# driver_board_one_module_pic_v2.net
KiCad netlist of a schematic drawn in EAGLE
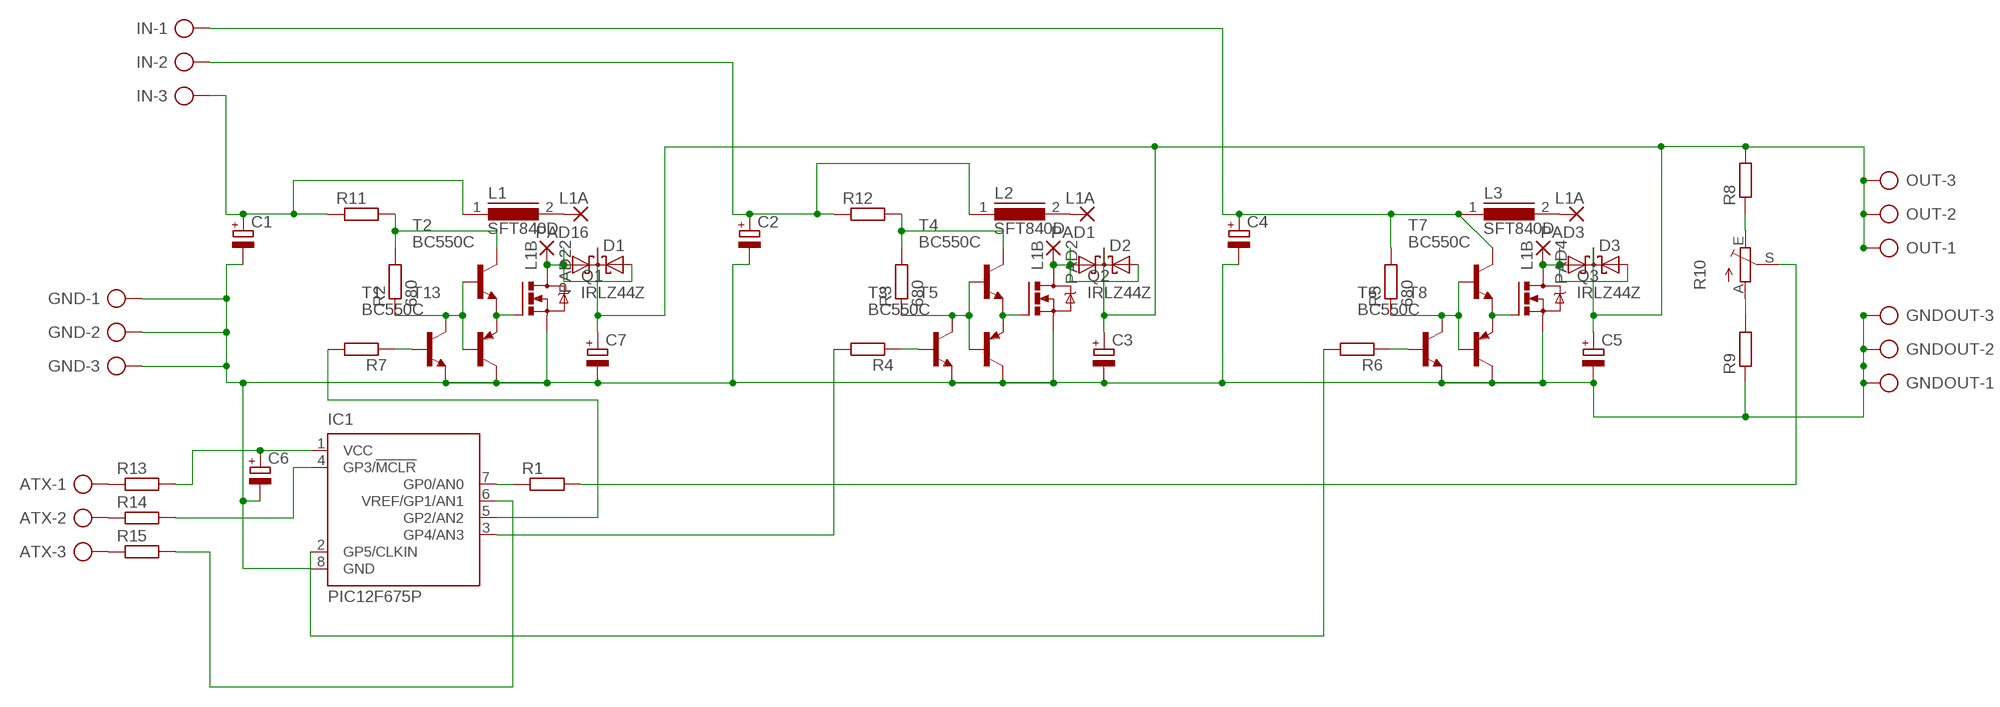
[diagram p0: schematic, sheet 1]

(export (version "E")
  (design (tool "Eeschema 10.0.6"))
  (components
    (comp (ref "ATX")
      (value "AK300/3")
      (footprint "eagle-import:AK300_3")
      (libsource (lib "eagle-import") (part "AK300/3"))
    )
    (comp (ref "C1")
      (value "CPOL-EUE5-8.5")
      (footprint "eagle-import:E5-8,5")
      (libsource (lib "eagle-import") (part "CPOL-EUE5-8.5"))
    )
    (comp (ref "C2")
      (value "CPOL-EUE5-8.5")
      (footprint "eagle-import:E5-8,5")
      (libsource (lib "eagle-import") (part "CPOL-EUE5-8.5"))
    )
    (comp (ref "C3")
      (value "CPOL-EUE5-8.5")
      (footprint "eagle-import:E5-8,5")
      (libsource (lib "eagle-import") (part "CPOL-EUE5-8.5"))
    )
    (comp (ref "C4")
      (value "CPOL-EUE5-8.5")
      (footprint "eagle-import:E5-8,5")
      (libsource (lib "eagle-import") (part "CPOL-EUE5-8.5"))
    )
    (comp (ref "C5")
      (value "CPOL-EUE5-8.5")
      (footprint "eagle-import:E5-8,5")
      (libsource (lib "eagle-import") (part "CPOL-EUE5-8.5"))
    )
    (comp (ref "C6")
      (value "CPOL-EUE5-8.5")
      (footprint "eagle-import:E5-8,5")
      (libsource (lib "eagle-import") (part "CPOL-EUE5-8.5"))
    )
    (comp (ref "C7")
      (value "CPOL-EUE5-8.5")
      (footprint "eagle-import:E5-8,5")
      (libsource (lib "eagle-import") (part "CPOL-EUE5-8.5"))
    )
    (comp (ref "D1")
      (value "DIODE_2SCHOTTKY-SOT93V")
      (footprint "eagle-import:SOT93S")
      (libsource (lib "eagle-import") (part "DIODE_2SCHOTTKY-SOT93V"))
    )
    (comp (ref "D2")
      (value "DIODE_2SCHOTTKY-SOT93V")
      (footprint "eagle-import:SOT93S")
      (libsource (lib "eagle-import") (part "DIODE_2SCHOTTKY-SOT93V"))
    )
    (comp (ref "D3")
      (value "DIODE_2SCHOTTKY-SOT93V")
      (footprint "eagle-import:SOT93S")
      (libsource (lib "eagle-import") (part "DIODE_2SCHOTTKY-SOT93V"))
    )
    (comp (ref "GND")
      (value "AK300/3")
      (footprint "eagle-import:AK300_3")
      (libsource (lib "eagle-import") (part "AK300/3"))
    )
    (comp (ref "GNDOUT")
      (value "AK300/3")
      (footprint "eagle-import:AK300_3")
      (libsource (lib "eagle-import") (part "AK300/3"))
    )
    (comp (ref "IC1")
      (value "PIC12F675P")
      (footprint "eagle-import:DIL8")
      (fields (field (name "MF") "MICROCHIP") (field (name "MPN") "PIC12F675-E/P"))
      (libsource (lib "eagle-import") (part "PIC12F675P"))
    )
    (comp (ref "IN")
      (value "AK300/3")
      (footprint "eagle-import:AK300_3")
      (libsource (lib "eagle-import") (part "AK300/3"))
    )
    (comp (ref "L1")
      (value "SFT840D")
      (footprint "eagle-import:SFT840D")
      (libsource (lib "eagle-import") (part "SFT840D"))
    )
    (comp (ref "L2")
      (value "SFT840D")
      (footprint "eagle-import:SFT840D")
      (libsource (lib "eagle-import") (part "SFT840D"))
    )
    (comp (ref "L3")
      (value "SFT840D")
      (footprint "eagle-import:SFT840D")
      (libsource (lib "eagle-import") (part "SFT840D"))
    )
    (comp (ref "OUT")
      (value "AK300/3")
      (footprint "eagle-import:AK300_3")
      (libsource (lib "eagle-import") (part "AK300/3"))
    )
    (comp (ref "PAD1")
      (value "L1A")
      (footprint "eagle-import:3,81_1,1")
      (libsource (lib "eagle-import") (part "3,81/1,1"))
    )
    (comp (ref "PAD2")
      (value "L1B")
      (footprint "eagle-import:3,81_1,1")
      (libsource (lib "eagle-import") (part "3,81/1,1"))
    )
    (comp (ref "PAD3")
      (value "L1A")
      (footprint "eagle-import:3,81_1,1")
      (libsource (lib "eagle-import") (part "3,81/1,1"))
    )
    (comp (ref "PAD4")
      (value "L1B")
      (footprint "eagle-import:3,81_1,1")
      (libsource (lib "eagle-import") (part "3,81/1,1"))
    )
    (comp (ref "PAD16")
      (value "L1A")
      (footprint "eagle-import:3,81_1,1")
      (libsource (lib "eagle-import") (part "3,81/1,1"))
    )
    (comp (ref "PAD22")
      (value "L1B")
      (footprint "eagle-import:3,81_1,1")
      (libsource (lib "eagle-import") (part "3,81/1,1"))
    )
    (comp (ref "Q1")
      (value "IRLZ44Z")
      (footprint "eagle-import:TO220BH")
      (libsource (lib "eagle-import") (part "IRLZ44Z"))
    )
    (comp (ref "Q2")
      (value "IRLZ44Z")
      (footprint "eagle-import:TO220BH")
      (libsource (lib "eagle-import") (part "IRLZ44Z"))
    )
    (comp (ref "Q3")
      (value "IRLZ44Z")
      (footprint "eagle-import:TO220BH")
      (libsource (lib "eagle-import") (part "IRLZ44Z"))
    )
    (comp (ref "R1")
      (value "R-EU_0207/7")
      (footprint "eagle-import:0207_7")
      (libsource (lib "eagle-import") (part "resistor_R-EU_0207/7"))
    )
    (comp (ref "R2")
      (value "680")
      (footprint "eagle-import:0204_7")
      (libsource (lib "eagle-import") (part "resistor_R-EU_0204/7"))
    )
    (comp (ref "R3")
      (value "680")
      (footprint "eagle-import:0204_7")
      (libsource (lib "eagle-import") (part "resistor_R-EU_0204/7"))
    )
    (comp (ref "R4")
      (value "R-EU_0207/10")
      (footprint "eagle-import:0207_10")
      (libsource (lib "eagle-import") (part "R-EU_0207/10"))
    )
    (comp (ref "R5")
      (value "680")
      (footprint "eagle-import:0204_7")
      (libsource (lib "eagle-import") (part "resistor_R-EU_0204/7"))
    )
    (comp (ref "R6")
      (value "R-EU_0207/10")
      (footprint "eagle-import:0207_10")
      (libsource (lib "eagle-import") (part "R-EU_0207/10"))
    )
    (comp (ref "R7")
      (value "R-EU_0207/7")
      (footprint "eagle-import:0207_7")
      (libsource (lib "eagle-import") (part "resistor_R-EU_0207/7"))
    )
    (comp (ref "R8")
      (value "R-EU_0207/7")
      (footprint "eagle-import:0207_7")
      (libsource (lib "eagle-import") (part "resistor_R-EU_0207/7"))
    )
    (comp (ref "R9")
      (value "R-EU_0207/7")
      (footprint "eagle-import:0207_7")
      (libsource (lib "eagle-import") (part "resistor_R-EU_0207/7"))
    )
    (comp (ref "R10")
      (value "TRIM_EU-RJ9W")
      (footprint "eagle-import:RJ9W")
      (libsource (lib "eagle-import") (part "TRIM_EU-RJ9W"))
    )
    (comp (ref "R11")
      (value "R-EU_0207/10")
      (footprint "eagle-import:0207_10")
      (libsource (lib "eagle-import") (part "resistor_R-EU_0207/10"))
    )
    (comp (ref "R12")
      (value "R-EU_0207/15")
      (footprint "eagle-import:0207_15")
      (libsource (lib "eagle-import") (part "R-EU_0207/15"))
    )
    (comp (ref "R13")
      (value "R-EU_0207/10")
      (footprint "eagle-import:0207_10")
      (libsource (lib "eagle-import") (part "resistor_R-EU_0207/10"))
    )
    (comp (ref "R14")
      (value "R-EU_0207/10")
      (footprint "eagle-import:0207_10")
      (libsource (lib "eagle-import") (part "resistor_R-EU_0207/10"))
    )
    (comp (ref "R15")
      (value "R-EU_0207/10")
      (footprint "eagle-import:0207_10")
      (libsource (lib "eagle-import") (part "resistor_R-EU_0207/10"))
    )
    (comp (ref "T1")
      (value "BC550C")
      (footprint "eagle-import:TO92-EBC")
      (libsource (lib "eagle-import") (part "BC550C"))
    )
    (comp (ref "T2")
      (value "BC550C")
      (footprint "eagle-import:TO92-EBC")
      (libsource (lib "eagle-import") (part "BC550C"))
    )
    (comp (ref "T3")
      (value "BC550C")
      (footprint "eagle-import:TO92-EBC")
      (libsource (lib "eagle-import") (part "BC550C"))
    )
    (comp (ref "T4")
      (value "BC550C")
      (footprint "eagle-import:TO92-EBC")
      (libsource (lib "eagle-import") (part "BC550C"))
    )
    (comp (ref "T5")
      (value "BC557C-PNP-TO92-EBC")
      (footprint "eagle-import:TO92-EBC")
      (libsource (lib "eagle-import") (part "-PNP-TO92-EBCBC557C"))
    )
    (comp (ref "T6")
      (value "BC550C")
      (footprint "eagle-import:TO92-EBC")
      (libsource (lib "eagle-import") (part "BC550C"))
    )
    (comp (ref "T7")
      (value "BC550C")
      (footprint "eagle-import:TO92-EBC")
      (libsource (lib "eagle-import") (part "BC550C"))
    )
    (comp (ref "T8")
      (value "BC557C-PNP-TO92-EBC")
      (footprint "eagle-import:TO92-EBC")
      (libsource (lib "eagle-import") (part "-PNP-TO92-EBCBC557C"))
    )
    (comp (ref "T13")
      (value "BC557C-PNP-TO92-EBC")
      (footprint "eagle-import:TO92-EBC")
      (libsource (lib "eagle-import") (part "-PNP-TO92-EBCBC557C"))
    )
  )
  (nets
    (net (code "1") (name "Net-(ATXA-KL)") (class "Default")
      (node (ref "ATX") (pin "1") (pinfunction "KL_1") (pintype "passive"))
      (node (ref "R13") (pin "1") (pinfunction "1_1") (pintype "passive"))
    )
    (net (code "2") (name "Net-(ATXB-KL)") (class "Default")
      (node (ref "ATX") (pin "2") (pinfunction "KL_2") (pintype "passive"))
      (node (ref "R14") (pin "1") (pinfunction "1_1") (pintype "passive"))
    )
    (net (code "3") (name "Net-(ATXC-KL)") (class "Default")
      (node (ref "ATX") (pin "3") (pinfunction "KL_3") (pintype "passive"))
      (node (ref "R15") (pin "1") (pinfunction "1_1") (pintype "passive"))
    )
    (net (code "4") (name "Net-(GNDA-KL)") (class "Default")
      (node (ref "C1") (pin "-") (pinfunction "-_-") (pintype "passive"))
      (node (ref "C2") (pin "-") (pinfunction "-_-") (pintype "passive"))
      (node (ref "C3") (pin "-") (pinfunction "-_-") (pintype "passive"))
      (node (ref "C4") (pin "-") (pinfunction "-_-") (pintype "passive"))
      (node (ref "C5") (pin "-") (pinfunction "-_-") (pintype "passive"))
      (node (ref "C6") (pin "-") (pinfunction "-_-") (pintype "passive"))
      (node (ref "C7") (pin "-") (pinfunction "-_-") (pintype "passive"))
      (node (ref "GND") (pin "1") (pinfunction "KL_1") (pintype "passive"))
      (node (ref "GND") (pin "2") (pinfunction "KL_2") (pintype "passive"))
      (node (ref "GND") (pin "3") (pinfunction "KL_3") (pintype "passive"))
      (node (ref "GNDOUT") (pin "1") (pinfunction "KL_1") (pintype "passive"))
      (node (ref "GNDOUT") (pin "2") (pinfunction "KL_2") (pintype "passive"))
      (node (ref "GNDOUT") (pin "3") (pinfunction "KL_3") (pintype "passive"))
      (node (ref "IC1") (pin "8") (pinfunction "GND_8") (pintype "power_in"))
      (node (ref "Q1") (pin "S") (pinfunction "S_S") (pintype "passive"))
      (node (ref "Q2") (pin "S") (pinfunction "S_S") (pintype "passive"))
      (node (ref "Q3") (pin "S") (pinfunction "S_S") (pintype "passive"))
      (node (ref "R9") (pin "1") (pinfunction "1_1") (pintype "passive"))
      (node (ref "T1") (pin "E") (pinfunction "E_E") (pintype "passive"))
      (node (ref "T13") (pin "C") (pinfunction "C_C") (pintype "passive"))
      (node (ref "T3") (pin "E") (pinfunction "E_E") (pintype "passive"))
      (node (ref "T5") (pin "C") (pinfunction "C_C") (pintype "passive"))
      (node (ref "T6") (pin "E") (pinfunction "E_E") (pintype "passive"))
      (node (ref "T8") (pin "C") (pinfunction "C_C") (pintype "passive"))
    )
    (net (code "5") (name "Net-(IC1-GP0{slash}AN0)") (class "Default")
      (node (ref "IC1") (pin "7") (pinfunction "GP0/AN0_7") (pintype "bidirectional"))
      (node (ref "R1") (pin "1") (pinfunction "1_1") (pintype "passive"))
    )
    (net (code "6") (name "Net-(IC1-GP2{slash}AN2)") (class "Default")
      (node (ref "IC1") (pin "5") (pinfunction "GP2/AN2_5") (pintype "bidirectional"))
      (node (ref "R7") (pin "2") (pinfunction "2_2") (pintype "passive"))
    )
    (net (code "7") (name "Net-(IC1-GP3{slash}~{MCLR})") (class "Default")
      (node (ref "IC1") (pin "4") (pinfunction "GP3/~{MCLR}_4") (pintype "input"))
      (node (ref "R14") (pin "2") (pinfunction "2_2") (pintype "passive"))
    )
    (net (code "8") (name "Net-(IC1-GP4{slash}AN3)") (class "Default")
      (node (ref "IC1") (pin "3") (pinfunction "GP4/AN3_3") (pintype "bidirectional"))
      (node (ref "R4") (pin "2") (pinfunction "2_2") (pintype "passive"))
    )
    (net (code "9") (name "Net-(IC1-GP5{slash}CLKIN)") (class "Default")
      (node (ref "IC1") (pin "2") (pinfunction "GP5/CLKIN_2") (pintype "bidirectional"))
      (node (ref "R6") (pin "2") (pinfunction "2_2") (pintype "passive"))
    )
    (net (code "10") (name "Net-(IC1-VCC)") (class "Default")
      (node (ref "C6") (pin "+") (pinfunction "+_+") (pintype "passive"))
      (node (ref "IC1") (pin "1") (pinfunction "VCC_1") (pintype "power_in"))
      (node (ref "R13") (pin "2") (pinfunction "2_2") (pintype "passive"))
    )
    (net (code "11") (name "Net-(IC1-VREF{slash}GP1{slash}AN1)") (class "Default")
      (node (ref "IC1") (pin "6") (pinfunction "VREF/GP1/AN1_6") (pintype "bidirectional"))
      (node (ref "R15") (pin "2") (pinfunction "2_2") (pintype "passive"))
    )
    (net (code "12") (name "Net-(INA-KL)") (class "Default")
      (node (ref "C4") (pin "+") (pinfunction "+_+") (pintype "passive"))
      (node (ref "IN") (pin "1") (pinfunction "KL_1") (pintype "passive"))
      (node (ref "L3") (pin "1") (pinfunction "1_1") (pintype "passive"))
      (node (ref "R5") (pin "2") (pinfunction "2_2") (pintype "passive"))
      (node (ref "T7") (pin "C") (pinfunction "C_C") (pintype "passive"))
    )
    (net (code "13") (name "Net-(INB-KL)") (class "Default")
      (node (ref "C2") (pin "+") (pinfunction "+_+") (pintype "passive"))
      (node (ref "IN") (pin "2") (pinfunction "KL_2") (pintype "passive"))
      (node (ref "L2") (pin "1") (pinfunction "1_1") (pintype "passive"))
      (node (ref "R12") (pin "1") (pinfunction "1_1") (pintype "passive"))
    )
    (net (code "14") (name "Net-(INC-KL)") (class "Default")
      (node (ref "C1") (pin "+") (pinfunction "+_+") (pintype "passive"))
      (node (ref "IN") (pin "3") (pinfunction "KL_3") (pintype "passive"))
      (node (ref "L1") (pin "1") (pinfunction "1_1") (pintype "passive"))
      (node (ref "R11") (pin "1") (pinfunction "1_1") (pintype "passive"))
    )
    (net (code "15") (name "Net-(OUTA-KL)") (class "Default")
      (node (ref "C3") (pin "+") (pinfunction "+_+") (pintype "passive"))
      (node (ref "C5") (pin "+") (pinfunction "+_+") (pintype "passive"))
      (node (ref "C7") (pin "+") (pinfunction "+_+") (pintype "passive"))
      (node (ref "D1") (pin "C") (pinfunction "C_C") (pintype "passive"))
      (node (ref "D2") (pin "C") (pinfunction "C_C") (pintype "passive"))
      (node (ref "D3") (pin "C") (pinfunction "C_C") (pintype "passive"))
      (node (ref "OUT") (pin "1") (pinfunction "KL_1") (pintype "passive"))
      (node (ref "OUT") (pin "2") (pinfunction "KL_2") (pintype "passive"))
      (node (ref "OUT") (pin "3") (pinfunction "KL_3") (pintype "passive"))
      (node (ref "R8") (pin "2") (pinfunction "2_2") (pintype "passive"))
    )
    (net (code "16") (name "Net-(PAD1-P)") (class "Default")
      (node (ref "L2") (pin "2") (pinfunction "2_2") (pintype "passive"))
      (node (ref "PAD1") (pin "1") (pinfunction "P_1") (pintype "passive"))
    )
    (net (code "17") (name "Net-(PAD2-P)") (class "Default")
      (node (ref "D2") (pin "A1") (pinfunction "A1_A1") (pintype "passive"))
      (node (ref "D2") (pin "A2") (pinfunction "A2_A2") (pintype "passive"))
      (node (ref "PAD2") (pin "1") (pinfunction "P_1") (pintype "passive"))
      (node (ref "Q2") (pin "D") (pinfunction "D_D") (pintype "passive"))
    )
    (net (code "18") (name "Net-(PAD3-P)") (class "Default")
      (node (ref "L3") (pin "2") (pinfunction "2_2") (pintype "passive"))
      (node (ref "PAD3") (pin "1") (pinfunction "P_1") (pintype "passive"))
    )
    (net (code "19") (name "Net-(PAD4-P)") (class "Default")
      (node (ref "D3") (pin "A1") (pinfunction "A1_A1") (pintype "passive"))
      (node (ref "D3") (pin "A2") (pinfunction "A2_A2") (pintype "passive"))
      (node (ref "PAD4") (pin "1") (pinfunction "P_1") (pintype "passive"))
      (node (ref "Q3") (pin "D") (pinfunction "D_D") (pintype "passive"))
    )
    (net (code "20") (name "Net-(PAD16-P)") (class "Default")
      (node (ref "L1") (pin "2") (pinfunction "2_2") (pintype "passive"))
      (node (ref "PAD16") (pin "1") (pinfunction "P_1") (pintype "passive"))
    )
    (net (code "21") (name "Net-(PAD22-P)") (class "Default")
      (node (ref "D1") (pin "A1") (pinfunction "A1_A1") (pintype "passive"))
      (node (ref "D1") (pin "A2") (pinfunction "A2_A2") (pintype "passive"))
      (node (ref "PAD22") (pin "1") (pinfunction "P_1") (pintype "passive"))
      (node (ref "Q1") (pin "D") (pinfunction "D_D") (pintype "passive"))
    )
    (net (code "22") (name "Net-(Q1-PadG)") (class "Default")
      (node (ref "Q1") (pin "G") (pinfunction "G_G") (pintype "passive"))
      (node (ref "T13") (pin "E") (pinfunction "E_E") (pintype "passive"))
      (node (ref "T2") (pin "E") (pinfunction "E_E") (pintype "passive"))
    )
    (net (code "23") (name "Net-(Q2-PadG)") (class "Default")
      (node (ref "Q2") (pin "G") (pinfunction "G_G") (pintype "passive"))
      (node (ref "T4") (pin "E") (pinfunction "E_E") (pintype "passive"))
      (node (ref "T5") (pin "E") (pinfunction "E_E") (pintype "passive"))
    )
    (net (code "24") (name "Net-(Q3-PadG)") (class "Default")
      (node (ref "Q3") (pin "G") (pinfunction "G_G") (pintype "passive"))
      (node (ref "T7") (pin "E") (pinfunction "E_E") (pintype "passive"))
      (node (ref "T8") (pin "E") (pinfunction "E_E") (pintype "passive"))
    )
    (net (code "25") (name "Net-(R1-Pad2)") (class "Default")
      (node (ref "R1") (pin "2") (pinfunction "2_2") (pintype "passive"))
      (node (ref "R10") (pin "S") (pinfunction "S_S") (pintype "passive"))
    )
    (net (code "26") (name "Net-(R2-Pad1)") (class "Default")
      (node (ref "R2") (pin "1") (pinfunction "1_1") (pintype "passive"))
      (node (ref "T1") (pin "C") (pinfunction "C_C") (pintype "passive"))
      (node (ref "T13") (pin "B") (pinfunction "B_B") (pintype "passive"))
      (node (ref "T2") (pin "B") (pinfunction "B_B") (pintype "passive"))
    )
    (net (code "27") (name "Net-(R3-Pad1)") (class "Default")
      (node (ref "R3") (pin "1") (pinfunction "1_1") (pintype "passive"))
      (node (ref "T3") (pin "C") (pinfunction "C_C") (pintype "passive"))
      (node (ref "T4") (pin "B") (pinfunction "B_B") (pintype "passive"))
      (node (ref "T5") (pin "B") (pinfunction "B_B") (pintype "passive"))
    )
    (net (code "28") (name "Net-(R4-Pad1)") (class "Default")
      (node (ref "R4") (pin "1") (pinfunction "1_1") (pintype "passive"))
      (node (ref "T3") (pin "B") (pinfunction "B_B") (pintype "passive"))
    )
    (net (code "29") (name "Net-(R5-Pad1)") (class "Default")
      (node (ref "R5") (pin "1") (pinfunction "1_1") (pintype "passive"))
      (node (ref "T6") (pin "C") (pinfunction "C_C") (pintype "passive"))
      (node (ref "T7") (pin "B") (pinfunction "B_B") (pintype "passive"))
      (node (ref "T8") (pin "B") (pinfunction "B_B") (pintype "passive"))
    )
    (net (code "30") (name "Net-(R6-Pad1)") (class "Default")
      (node (ref "R6") (pin "1") (pinfunction "1_1") (pintype "passive"))
      (node (ref "T6") (pin "B") (pinfunction "B_B") (pintype "passive"))
    )
    (net (code "31") (name "Net-(R7-Pad1)") (class "Default")
      (node (ref "R7") (pin "1") (pinfunction "1_1") (pintype "passive"))
      (node (ref "T1") (pin "B") (pinfunction "B_B") (pintype "passive"))
    )
    (net (code "32") (name "Net-(R10-PadA)") (class "Default")
      (node (ref "R10") (pin "A") (pinfunction "A_A") (pintype "passive"))
      (node (ref "R9") (pin "2") (pinfunction "2_2") (pintype "passive"))
    )
    (net (code "33") (name "Net-(R10-PadE)") (class "Default")
      (node (ref "R10") (pin "E") (pinfunction "E_E") (pintype "passive"))
      (node (ref "R8") (pin "1") (pinfunction "1_1") (pintype "passive"))
    )
    (net (code "34") (name "Net-(R11-Pad2)") (class "Default")
      (node (ref "R11") (pin "2") (pinfunction "2_2") (pintype "passive"))
      (node (ref "R2") (pin "2") (pinfunction "2_2") (pintype "passive"))
      (node (ref "T2") (pin "C") (pinfunction "C_C") (pintype "passive"))
    )
    (net (code "35") (name "Net-(R12-Pad2)") (class "Default")
      (node (ref "R12") (pin "2") (pinfunction "2_2") (pintype "passive"))
      (node (ref "R3") (pin "2") (pinfunction "2_2") (pintype "passive"))
      (node (ref "T4") (pin "C") (pinfunction "C_C") (pintype "passive"))
    )
  )
)
